# PowerRouting.net
KiCad netlist of a schematic drawn in Altium Designer
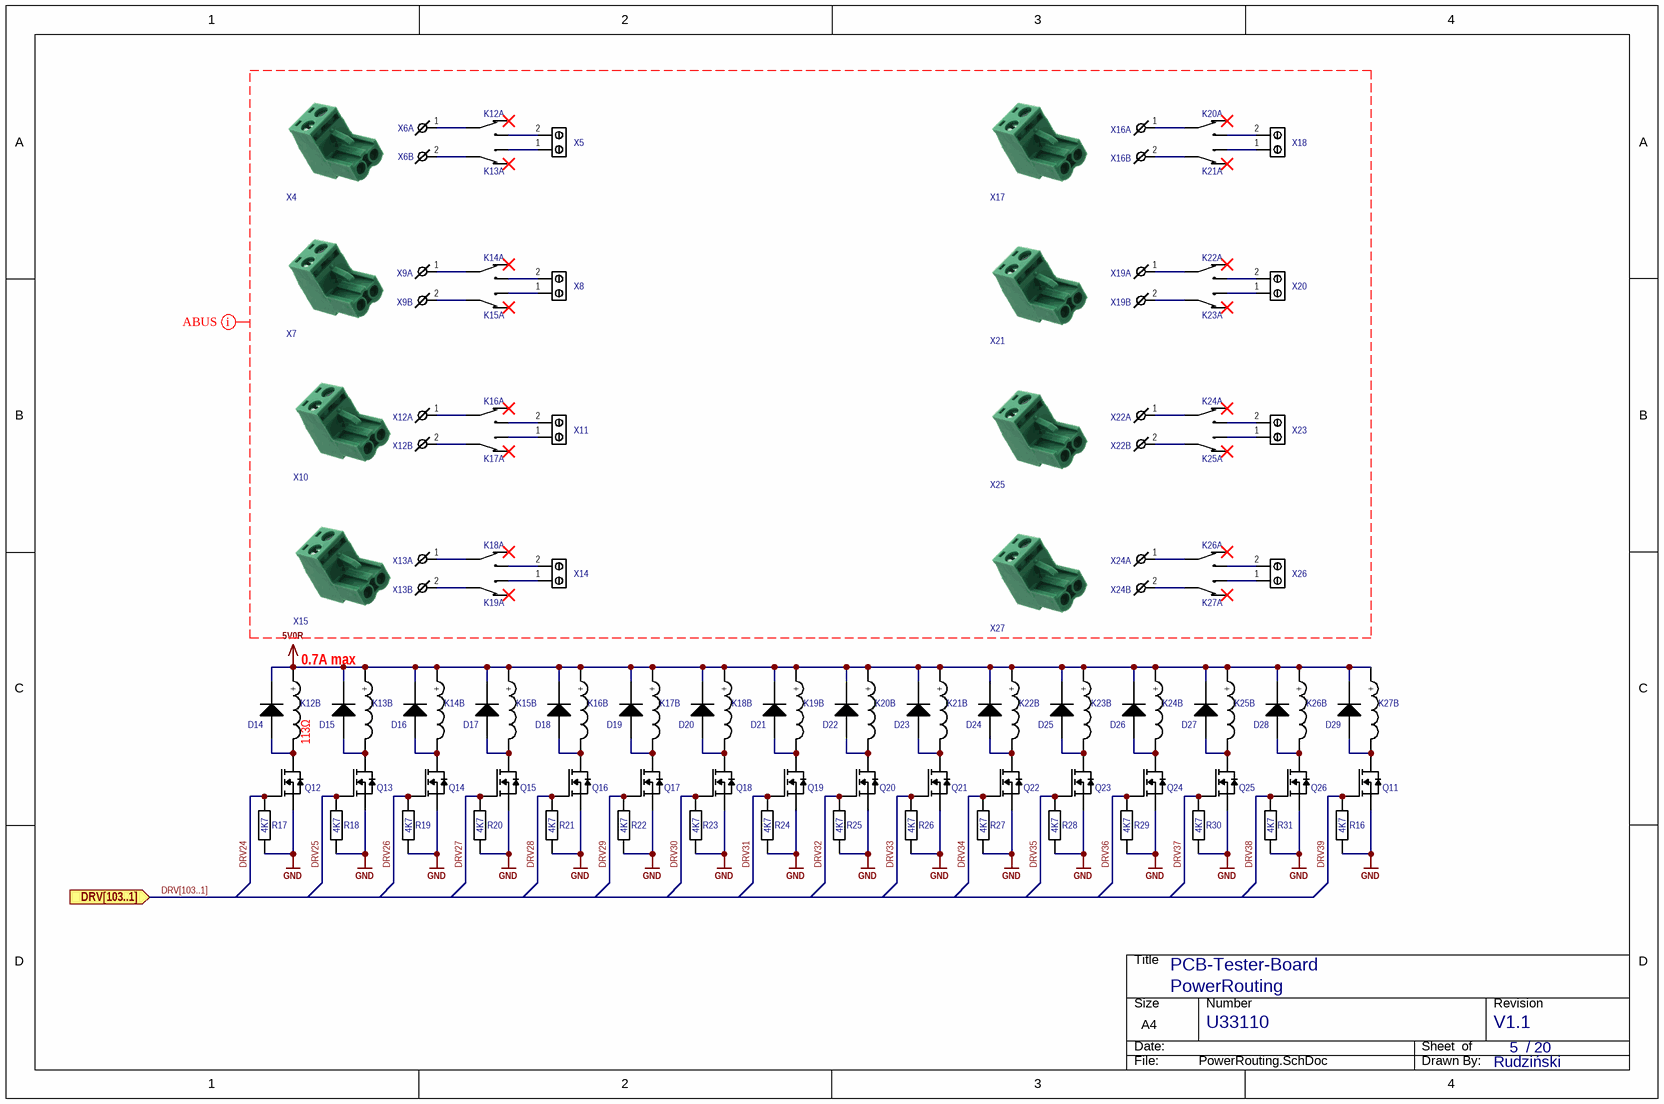
[diagram p0: PowerRouting.SchDoc]

(export (version "E")
  (design (tool "Eeschema 10.0.6"))
  (components
    (comp (ref "D14")
      (value "D")
      (footprint "SOD123")
      (description "DIODE GEN PURP 100V 300MA SOD123")
      (fields
        (field (name "02. DISTRIBUTOR PART NUMBER") "1N4148W-FDICT-ND")
        (field (name "07. MANUFACTURER  PART NUMBER") "1N4148W-7-F")
      )
      (libsource (lib "PCB-Tester-Board-V1") (part "1N4148W"))
    )
    (comp (ref "D15")
      (value "D")
      (footprint "SOD123")
      (description "DIODE GEN PURP 100V 300MA SOD123")
      (fields
        (field (name "02. DISTRIBUTOR PART NUMBER") "1N4148W-FDICT-ND")
        (field (name "07. MANUFACTURER  PART NUMBER") "1N4148W-7-F")
      )
      (libsource (lib "PCB-Tester-Board-V1") (part "1N4148W"))
    )
    (comp (ref "D16")
      (value "D")
      (footprint "SOD123")
      (description "DIODE GEN PURP 100V 300MA SOD123")
      (fields
        (field (name "02. DISTRIBUTOR PART NUMBER") "1N4148W-FDICT-ND")
        (field (name "07. MANUFACTURER  PART NUMBER") "1N4148W-7-F")
      )
      (libsource (lib "PCB-Tester-Board-V1") (part "1N4148W"))
    )
    (comp (ref "D17")
      (value "D")
      (footprint "SOD123")
      (description "DIODE GEN PURP 100V 300MA SOD123")
      (fields
        (field (name "02. DISTRIBUTOR PART NUMBER") "1N4148W-FDICT-ND")
        (field (name "07. MANUFACTURER  PART NUMBER") "1N4148W-7-F")
      )
      (libsource (lib "PCB-Tester-Board-V1") (part "1N4148W"))
    )
    (comp (ref "D18")
      (value "D")
      (footprint "SOD123")
      (description "DIODE GEN PURP 100V 300MA SOD123")
      (fields
        (field (name "02. DISTRIBUTOR PART NUMBER") "1N4148W-FDICT-ND")
        (field (name "07. MANUFACTURER  PART NUMBER") "1N4148W-7-F")
      )
      (libsource (lib "PCB-Tester-Board-V1") (part "1N4148W"))
    )
    (comp (ref "D19")
      (value "D")
      (footprint "SOD123")
      (description "DIODE GEN PURP 100V 300MA SOD123")
      (fields
        (field (name "02. DISTRIBUTOR PART NUMBER") "1N4148W-FDICT-ND")
        (field (name "07. MANUFACTURER  PART NUMBER") "1N4148W-7-F")
      )
      (libsource (lib "PCB-Tester-Board-V1") (part "1N4148W"))
    )
    (comp (ref "D20")
      (value "D")
      (footprint "SOD123")
      (description "DIODE GEN PURP 100V 300MA SOD123")
      (fields
        (field (name "02. DISTRIBUTOR PART NUMBER") "1N4148W-FDICT-ND")
        (field (name "07. MANUFACTURER  PART NUMBER") "1N4148W-7-F")
      )
      (libsource (lib "PCB-Tester-Board-V1") (part "1N4148W"))
    )
    (comp (ref "D21")
      (value "D")
      (footprint "SOD123")
      (description "DIODE GEN PURP 100V 300MA SOD123")
      (fields
        (field (name "02. DISTRIBUTOR PART NUMBER") "1N4148W-FDICT-ND")
        (field (name "07. MANUFACTURER  PART NUMBER") "1N4148W-7-F")
      )
      (libsource (lib "PCB-Tester-Board-V1") (part "1N4148W"))
    )
    (comp (ref "D22")
      (value "D")
      (footprint "SOD123")
      (description "DIODE GEN PURP 100V 300MA SOD123")
      (fields
        (field (name "02. DISTRIBUTOR PART NUMBER") "1N4148W-FDICT-ND")
        (field (name "07. MANUFACTURER  PART NUMBER") "1N4148W-7-F")
      )
      (libsource (lib "PCB-Tester-Board-V1") (part "1N4148W"))
    )
    (comp (ref "D23")
      (value "D")
      (footprint "SOD123")
      (description "DIODE GEN PURP 100V 300MA SOD123")
      (fields
        (field (name "02. DISTRIBUTOR PART NUMBER") "1N4148W-FDICT-ND")
        (field (name "07. MANUFACTURER  PART NUMBER") "1N4148W-7-F")
      )
      (libsource (lib "PCB-Tester-Board-V1") (part "1N4148W"))
    )
    (comp (ref "D24")
      (value "D")
      (footprint "SOD123")
      (description "DIODE GEN PURP 100V 300MA SOD123")
      (fields
        (field (name "02. DISTRIBUTOR PART NUMBER") "1N4148W-FDICT-ND")
        (field (name "07. MANUFACTURER  PART NUMBER") "1N4148W-7-F")
      )
      (libsource (lib "PCB-Tester-Board-V1") (part "1N4148W"))
    )
    (comp (ref "D25")
      (value "D")
      (footprint "SOD123")
      (description "DIODE GEN PURP 100V 300MA SOD123")
      (fields
        (field (name "02. DISTRIBUTOR PART NUMBER") "1N4148W-FDICT-ND")
        (field (name "07. MANUFACTURER  PART NUMBER") "1N4148W-7-F")
      )
      (libsource (lib "PCB-Tester-Board-V1") (part "1N4148W"))
    )
    (comp (ref "D26")
      (value "D")
      (footprint "SOD123")
      (description "DIODE GEN PURP 100V 300MA SOD123")
      (fields
        (field (name "02. DISTRIBUTOR PART NUMBER") "1N4148W-FDICT-ND")
        (field (name "07. MANUFACTURER  PART NUMBER") "1N4148W-7-F")
      )
      (libsource (lib "PCB-Tester-Board-V1") (part "1N4148W"))
    )
    (comp (ref "D27")
      (value "D")
      (footprint "SOD123")
      (description "DIODE GEN PURP 100V 300MA SOD123")
      (fields
        (field (name "02. DISTRIBUTOR PART NUMBER") "1N4148W-FDICT-ND")
        (field (name "07. MANUFACTURER  PART NUMBER") "1N4148W-7-F")
      )
      (libsource (lib "PCB-Tester-Board-V1") (part "1N4148W"))
    )
    (comp (ref "D28")
      (value "D")
      (footprint "SOD123")
      (description "DIODE GEN PURP 100V 300MA SOD123")
      (fields
        (field (name "02. DISTRIBUTOR PART NUMBER") "1N4148W-FDICT-ND")
        (field (name "07. MANUFACTURER  PART NUMBER") "1N4148W-7-F")
      )
      (libsource (lib "PCB-Tester-Board-V1") (part "1N4148W"))
    )
    (comp (ref "D29")
      (value "D")
      (footprint "SOD123")
      (description "DIODE GEN PURP 100V 300MA SOD123")
      (fields
        (field (name "02. DISTRIBUTOR PART NUMBER") "1N4148W-FDICT-ND")
        (field (name "07. MANUFACTURER  PART NUMBER") "1N4148W-7-F")
      )
      (libsource (lib "PCB-Tester-Board-V1") (part "1N4148W"))
    )
    (comp (ref "K12")
      (value "K")
      (footprint "HF118F005-1ZS1")
      (description "5V Power Relay, switch over")
      (fields
        (field (name "02. DISTRIBUTOR PART NUMBER") "176-2821")
        (field (name "07. MANUFACTURER  PART NUMBER") "HF118F/005-1ZS1T(136)")
        (field (name "COIL RESISTANCE") "113Ω")
        (field (name "13. CREATED DATE/NAME") "AUG2018/Hören")
      )
      (libsource (lib "chickenfood") (part "HF118F005-1ZS1"))
    )
    (comp (ref "K13")
      (value "K")
      (footprint "HF118F005-1ZS1")
      (description "5V Power Relay, switch over")
      (fields
        (field (name "02. DISTRIBUTOR PART NUMBER") "176-2821")
        (field (name "07. MANUFACTURER  PART NUMBER") "HF118F/005-1ZS1T(136)")
        (field (name "13. CREATED DATE/NAME") "AUG2018/Hören")
      )
      (libsource (lib "chickenfood") (part "HF118F005-1ZS1"))
    )
    (comp (ref "K14")
      (value "K")
      (footprint "HF118F005-1ZS1")
      (description "5V Power Relay, switch over")
      (fields
        (field (name "02. DISTRIBUTOR PART NUMBER") "176-2821")
        (field (name "07. MANUFACTURER  PART NUMBER") "HF118F/005-1ZS1T(136)")
        (field (name "13. CREATED DATE/NAME") "AUG2018/Hören")
      )
      (libsource (lib "chickenfood") (part "HF118F005-1ZS1"))
    )
    (comp (ref "K15")
      (value "K")
      (footprint "HF118F005-1ZS1")
      (description "5V Power Relay, switch over")
      (fields
        (field (name "02. DISTRIBUTOR PART NUMBER") "176-2821")
        (field (name "07. MANUFACTURER  PART NUMBER") "HF118F/005-1ZS1T(136)")
        (field (name "13. CREATED DATE/NAME") "AUG2018/Hören")
      )
      (libsource (lib "chickenfood") (part "HF118F005-1ZS1"))
    )
    (comp (ref "K16")
      (value "K")
      (footprint "HF118F005-1ZS1")
      (description "5V Power Relay, switch over")
      (fields
        (field (name "02. DISTRIBUTOR PART NUMBER") "176-2821")
        (field (name "07. MANUFACTURER  PART NUMBER") "HF118F/005-1ZS1T(136)")
        (field (name "13. CREATED DATE/NAME") "AUG2018/Hören")
      )
      (libsource (lib "chickenfood") (part "HF118F005-1ZS1"))
    )
    (comp (ref "K17")
      (value "K")
      (footprint "HF118F005-1ZS1")
      (description "5V Power Relay, switch over")
      (fields
        (field (name "02. DISTRIBUTOR PART NUMBER") "176-2821")
        (field (name "07. MANUFACTURER  PART NUMBER") "HF118F/005-1ZS1T(136)")
        (field (name "13. CREATED DATE/NAME") "AUG2018/Hören")
      )
      (libsource (lib "chickenfood") (part "HF118F005-1ZS1"))
    )
    (comp (ref "K18")
      (value "K")
      (footprint "HF118F005-1ZS1")
      (description "5V Power Relay, switch over")
      (fields
        (field (name "02. DISTRIBUTOR PART NUMBER") "176-2821")
        (field (name "07. MANUFACTURER  PART NUMBER") "HF118F/005-1ZS1T(136)")
        (field (name "13. CREATED DATE/NAME") "AUG2018/Hören")
      )
      (libsource (lib "chickenfood") (part "HF118F005-1ZS1"))
    )
    (comp (ref "K19")
      (value "K")
      (footprint "HF118F005-1ZS1")
      (description "5V Power Relay, switch over")
      (fields
        (field (name "02. DISTRIBUTOR PART NUMBER") "176-2821")
        (field (name "07. MANUFACTURER  PART NUMBER") "HF118F/005-1ZS1T(136)")
        (field (name "13. CREATED DATE/NAME") "AUG2018/Hören")
      )
      (libsource (lib "chickenfood") (part "HF118F005-1ZS1"))
    )
    (comp (ref "K20")
      (value "K")
      (footprint "HF118F005-1ZS1")
      (description "5V Power Relay, switch over")
      (fields
        (field (name "02. DISTRIBUTOR PART NUMBER") "176-2821")
        (field (name "07. MANUFACTURER  PART NUMBER") "HF118F/005-1ZS1T(136)")
        (field (name "13. CREATED DATE/NAME") "AUG2018/Hören")
      )
      (libsource (lib "chickenfood") (part "HF118F005-1ZS1"))
    )
    (comp (ref "K21")
      (value "K")
      (footprint "HF118F005-1ZS1")
      (description "5V Power Relay, switch over")
      (fields
        (field (name "02. DISTRIBUTOR PART NUMBER") "176-2821")
        (field (name "07. MANUFACTURER  PART NUMBER") "HF118F/005-1ZS1T(136)")
        (field (name "13. CREATED DATE/NAME") "AUG2018/Hören")
      )
      (libsource (lib "chickenfood") (part "HF118F005-1ZS1"))
    )
    (comp (ref "K22")
      (value "K")
      (footprint "HF118F005-1ZS1")
      (description "5V Power Relay, switch over")
      (fields
        (field (name "02. DISTRIBUTOR PART NUMBER") "176-2821")
        (field (name "07. MANUFACTURER  PART NUMBER") "HF118F/005-1ZS1T(136)")
        (field (name "13. CREATED DATE/NAME") "AUG2018/Hören")
      )
      (libsource (lib "chickenfood") (part "HF118F005-1ZS1"))
    )
    (comp (ref "K23")
      (value "K")
      (footprint "HF118F005-1ZS1")
      (description "5V Power Relay, switch over")
      (fields
        (field (name "02. DISTRIBUTOR PART NUMBER") "176-2821")
        (field (name "07. MANUFACTURER  PART NUMBER") "HF118F/005-1ZS1T(136)")
        (field (name "13. CREATED DATE/NAME") "AUG2018/Hören")
      )
      (libsource (lib "") (part "HF118F005-1ZS1_1"))
    )
    (comp (ref "K24")
      (value "K")
      (footprint "HF118F005-1ZS1")
      (description "5V Power Relay, switch over")
      (fields
        (field (name "02. DISTRIBUTOR PART NUMBER") "176-2821")
        (field (name "07. MANUFACTURER  PART NUMBER") "HF118F/005-1ZS1T(136)")
        (field (name "13. CREATED DATE/NAME") "AUG2018/Hören")
      )
      (libsource (lib "chickenfood") (part "HF118F005-1ZS1"))
    )
    (comp (ref "K25")
      (value "K")
      (footprint "HF118F005-1ZS1")
      (description "5V Power Relay, switch over")
      (fields
        (field (name "02. DISTRIBUTOR PART NUMBER") "176-2821")
        (field (name "07. MANUFACTURER  PART NUMBER") "HF118F/005-1ZS1T(136)")
        (field (name "13. CREATED DATE/NAME") "AUG2018/Hören")
      )
      (libsource (lib "") (part "HF118F005-1ZS1_1"))
    )
    (comp (ref "K26")
      (value "K")
      (footprint "HF118F005-1ZS1")
      (description "5V Power Relay, switch over")
      (fields
        (field (name "02. DISTRIBUTOR PART NUMBER") "176-2821")
        (field (name "07. MANUFACTURER  PART NUMBER") "HF118F/005-1ZS1T(136)")
        (field (name "13. CREATED DATE/NAME") "AUG2018/Hören")
      )
      (libsource (lib "chickenfood") (part "HF118F005-1ZS1"))
    )
    (comp (ref "K27")
      (value "K")
      (footprint "HF118F005-1ZS1")
      (description "5V Power Relay, switch over")
      (fields
        (field (name "02. DISTRIBUTOR PART NUMBER") "176-2821")
        (field (name "07. MANUFACTURER  PART NUMBER") "HF118F/005-1ZS1T(136)")
        (field (name "13. CREATED DATE/NAME") "AUG2018/Hören")
      )
      (libsource (lib "") (part "HF118F005-1ZS1_1"))
    )
    (comp (ref "Q11")
      (value "Q")
      (footprint "SOT23-3")
      (description "MOSFET N-CH 25V 680MA SOT-23")
      (fields
        (field (name "02. DISTRIBUTOR PART NUMBER") "FDV303NDKR-ND")
        (field (name "07. MANUFACTURER  PART NUMBER") "FDV303N")
        (field (name "13. CREATED DATE/NAME") "AUG 2018 / Hören")
      )
      (libsource (lib "SCT8-Board1") (part "FDV303N"))
    )
    (comp (ref "Q12")
      (value "Q")
      (footprint "SOT23-3")
      (description "MOSFET N-CH 25V 680MA SOT-23")
      (fields
        (field (name "02. DISTRIBUTOR PART NUMBER") "FDV303NDKR-ND")
        (field (name "07. MANUFACTURER  PART NUMBER") "FDV303N")
        (field (name "13. CREATED DATE/NAME") "AUG 2018 / Hören")
      )
      (libsource (lib "SCT8-Board1") (part "FDV303N"))
    )
    (comp (ref "Q13")
      (value "Q")
      (footprint "SOT23-3")
      (description "MOSFET N-CH 25V 680MA SOT-23")
      (fields
        (field (name "02. DISTRIBUTOR PART NUMBER") "FDV303NDKR-ND")
        (field (name "07. MANUFACTURER  PART NUMBER") "FDV303N")
        (field (name "13. CREATED DATE/NAME") "AUG 2018 / Hören")
      )
      (libsource (lib "SCT8-Board1") (part "FDV303N"))
    )
    (comp (ref "Q14")
      (value "Q")
      (footprint "SOT23-3")
      (description "MOSFET N-CH 25V 680MA SOT-23")
      (fields
        (field (name "02. DISTRIBUTOR PART NUMBER") "FDV303NDKR-ND")
        (field (name "07. MANUFACTURER  PART NUMBER") "FDV303N")
        (field (name "13. CREATED DATE/NAME") "AUG 2018 / Hören")
      )
      (libsource (lib "SCT8-Board1") (part "FDV303N"))
    )
    (comp (ref "Q15")
      (value "Q")
      (footprint "SOT23-3")
      (description "MOSFET N-CH 25V 680MA SOT-23")
      (fields
        (field (name "02. DISTRIBUTOR PART NUMBER") "FDV303NDKR-ND")
        (field (name "07. MANUFACTURER  PART NUMBER") "FDV303N")
        (field (name "13. CREATED DATE/NAME") "AUG 2018 / Hören")
      )
      (libsource (lib "SCT8-Board1") (part "FDV303N"))
    )
    (comp (ref "Q16")
      (value "Q")
      (footprint "SOT23-3")
      (description "MOSFET N-CH 25V 680MA SOT-23")
      (fields
        (field (name "02. DISTRIBUTOR PART NUMBER") "FDV303NDKR-ND")
        (field (name "07. MANUFACTURER  PART NUMBER") "FDV303N")
        (field (name "13. CREATED DATE/NAME") "AUG 2018 / Hören")
      )
      (libsource (lib "SCT8-Board1") (part "FDV303N"))
    )
    (comp (ref "Q17")
      (value "Q")
      (footprint "SOT23-3")
      (description "MOSFET N-CH 25V 680MA SOT-23")
      (fields
        (field (name "02. DISTRIBUTOR PART NUMBER") "FDV303NDKR-ND")
        (field (name "07. MANUFACTURER  PART NUMBER") "FDV303N")
        (field (name "13. CREATED DATE/NAME") "AUG 2018 / Hören")
      )
      (libsource (lib "SCT8-Board1") (part "FDV303N"))
    )
    (comp (ref "Q18")
      (value "Q")
      (footprint "SOT23-3")
      (description "MOSFET N-CH 25V 680MA SOT-23")
      (fields
        (field (name "02. DISTRIBUTOR PART NUMBER") "FDV303NDKR-ND")
        (field (name "07. MANUFACTURER  PART NUMBER") "FDV303N")
        (field (name "13. CREATED DATE/NAME") "AUG 2018 / Hören")
      )
      (libsource (lib "SCT8-Board1") (part "FDV303N"))
    )
    (comp (ref "Q19")
      (value "Q")
      (footprint "SOT23-3")
      (description "MOSFET N-CH 25V 680MA SOT-23")
      (fields
        (field (name "02. DISTRIBUTOR PART NUMBER") "FDV303NDKR-ND")
        (field (name "07. MANUFACTURER  PART NUMBER") "FDV303N")
        (field (name "13. CREATED DATE/NAME") "AUG 2018 / Hören")
      )
      (libsource (lib "SCT8-Board1") (part "FDV303N"))
    )
    (comp (ref "Q20")
      (value "Q")
      (footprint "SOT23-3")
      (description "MOSFET N-CH 25V 680MA SOT-23")
      (fields
        (field (name "02. DISTRIBUTOR PART NUMBER") "FDV303NDKR-ND")
        (field (name "07. MANUFACTURER  PART NUMBER") "FDV303N")
        (field (name "13. CREATED DATE/NAME") "AUG 2018 / Hören")
      )
      (libsource (lib "SCT8-Board1") (part "FDV303N"))
    )
    (comp (ref "Q21")
      (value "Q")
      (footprint "SOT23-3")
      (description "MOSFET N-CH 25V 680MA SOT-23")
      (fields
        (field (name "02. DISTRIBUTOR PART NUMBER") "FDV303NDKR-ND")
        (field (name "07. MANUFACTURER  PART NUMBER") "FDV303N")
        (field (name "13. CREATED DATE/NAME") "AUG 2018 / Hören")
      )
      (libsource (lib "SCT8-Board1") (part "FDV303N"))
    )
    (comp (ref "Q22")
      (value "Q")
      (footprint "SOT23-3")
      (description "MOSFET N-CH 25V 680MA SOT-23")
      (fields
        (field (name "02. DISTRIBUTOR PART NUMBER") "FDV303NDKR-ND")
        (field (name "07. MANUFACTURER  PART NUMBER") "FDV303N")
        (field (name "13. CREATED DATE/NAME") "AUG 2018 / Hören")
      )
      (libsource (lib "SCT8-Board1") (part "FDV303N"))
    )
    (comp (ref "Q23")
      (value "Q")
      (footprint "SOT23-3")
      (description "MOSFET N-CH 25V 680MA SOT-23")
      (fields
        (field (name "02. DISTRIBUTOR PART NUMBER") "FDV303NDKR-ND")
        (field (name "07. MANUFACTURER  PART NUMBER") "FDV303N")
        (field (name "13. CREATED DATE/NAME") "AUG 2018 / Hören")
      )
      (libsource (lib "SCT8-Board1") (part "FDV303N"))
    )
    (comp (ref "Q24")
      (value "Q")
      (footprint "SOT23-3")
      (description "MOSFET N-CH 25V 680MA SOT-23")
      (fields
        (field (name "02. DISTRIBUTOR PART NUMBER") "FDV303NDKR-ND")
        (field (name "07. MANUFACTURER  PART NUMBER") "FDV303N")
        (field (name "13. CREATED DATE/NAME") "AUG 2018 / Hören")
      )
      (libsource (lib "SCT8-Board1") (part "FDV303N"))
    )
    (comp (ref "Q25")
      (value "Q")
      (footprint "SOT23-3")
      (description "MOSFET N-CH 25V 680MA SOT-23")
      (fields
        (field (name "02. DISTRIBUTOR PART NUMBER") "FDV303NDKR-ND")
        (field (name "07. MANUFACTURER  PART NUMBER") "FDV303N")
        (field (name "13. CREATED DATE/NAME") "AUG 2018 / Hören")
      )
      (libsource (lib "SCT8-Board1") (part "FDV303N"))
    )
    (comp (ref "Q26")
      (value "Q")
      (footprint "SOT23-3")
      (description "MOSFET N-CH 25V 680MA SOT-23")
      (fields
        (field (name "02. DISTRIBUTOR PART NUMBER") "FDV303NDKR-ND")
        (field (name "07. MANUFACTURER  PART NUMBER") "FDV303N")
        (field (name "13. CREATED DATE/NAME") "AUG 2018 / Hören")
      )
      (libsource (lib "SCT8-Board1") (part "FDV303N"))
    )
    (comp (ref "R16")
      (value "4K7")
      (footprint "R0603 Reflow")
      (description "RES SMD 4.7K OHM 1% 1/10W 0603")
      (fields
        (field (name "TOLERANCE") "±1%")
        (field (name "02. DISTRIBUTOR PART NUMBER") "311-4.70KHRCT-ND")
        (field (name "13. CREATED DATE/NAME") "AUG2018/Hören")
      )
      (libsource (lib "chickenfood") (part "R"))
    )
    (comp (ref "R17")
      (value "4K7")
      (footprint "R0603 Reflow")
      (description "RES SMD 4.7K OHM 1% 1/10W 0603")
      (fields
        (field (name "TOLERANCE") "±1%")
        (field (name "02. DISTRIBUTOR PART NUMBER") "311-4.70KHRCT-ND")
        (field (name "13. CREATED DATE/NAME") "AUG2018/Hören")
      )
      (libsource (lib "chickenfood") (part "R"))
    )
    (comp (ref "R18")
      (value "4K7")
      (footprint "R0603 Reflow")
      (description "RES SMD 4.7K OHM 1% 1/10W 0603")
      (fields
        (field (name "TOLERANCE") "±1%")
        (field (name "02. DISTRIBUTOR PART NUMBER") "311-4.70KHRCT-ND")
        (field (name "13. CREATED DATE/NAME") "AUG2018/Hören")
      )
      (libsource (lib "chickenfood") (part "R"))
    )
    (comp (ref "R19")
      (value "4K7")
      (footprint "R0603 Reflow")
      (description "RES SMD 4.7K OHM 1% 1/10W 0603")
      (fields
        (field (name "TOLERANCE") "±1%")
        (field (name "02. DISTRIBUTOR PART NUMBER") "311-4.70KHRCT-ND")
        (field (name "13. CREATED DATE/NAME") "AUG2018/Hören")
      )
      (libsource (lib "chickenfood") (part "R"))
    )
    (comp (ref "R20")
      (value "4K7")
      (footprint "R0603 Reflow")
      (description "RES SMD 4.7K OHM 1% 1/10W 0603")
      (fields
        (field (name "TOLERANCE") "±1%")
        (field (name "02. DISTRIBUTOR PART NUMBER") "311-4.70KHRCT-ND")
        (field (name "13. CREATED DATE/NAME") "AUG2018/Hören")
      )
      (libsource (lib "chickenfood") (part "R"))
    )
    (comp (ref "R21")
      (value "4K7")
      (footprint "R0603 Reflow")
      (description "RES SMD 4.7K OHM 1% 1/10W 0603")
      (fields
        (field (name "TOLERANCE") "±1%")
        (field (name "02. DISTRIBUTOR PART NUMBER") "311-4.70KHRCT-ND")
        (field (name "13. CREATED DATE/NAME") "AUG2018/Hören")
      )
      (libsource (lib "chickenfood") (part "R"))
    )
    (comp (ref "R22")
      (value "4K7")
      (footprint "R0603 Reflow")
      (description "RES SMD 4.7K OHM 1% 1/10W 0603")
      (fields
        (field (name "TOLERANCE") "±1%")
        (field (name "02. DISTRIBUTOR PART NUMBER") "311-4.70KHRCT-ND")
        (field (name "13. CREATED DATE/NAME") "AUG2018/Hören")
      )
      (libsource (lib "chickenfood") (part "R"))
    )
    (comp (ref "R23")
      (value "4K7")
      (footprint "R0603 Reflow")
      (description "RES SMD 4.7K OHM 1% 1/10W 0603")
      (fields
        (field (name "TOLERANCE") "±1%")
        (field (name "02. DISTRIBUTOR PART NUMBER") "311-4.70KHRCT-ND")
        (field (name "13. CREATED DATE/NAME") "AUG2018/Hören")
      )
      (libsource (lib "chickenfood") (part "R"))
    )
    (comp (ref "R24")
      (value "4K7")
      (footprint "R0603 Reflow")
      (description "RES SMD 4.7K OHM 1% 1/10W 0603")
      (fields
        (field (name "TOLERANCE") "±1%")
        (field (name "02. DISTRIBUTOR PART NUMBER") "311-4.70KHRCT-ND")
        (field (name "13. CREATED DATE/NAME") "AUG2018/Hören")
      )
      (libsource (lib "chickenfood") (part "R"))
    )
    (comp (ref "R25")
      (value "4K7")
      (footprint "R0603 Reflow")
      (description "RES SMD 4.7K OHM 1% 1/10W 0603")
      (fields
        (field (name "TOLERANCE") "±1%")
        (field (name "02. DISTRIBUTOR PART NUMBER") "311-4.70KHRCT-ND")
        (field (name "13. CREATED DATE/NAME") "AUG2018/Hören")
      )
      (libsource (lib "chickenfood") (part "R"))
    )
    (comp (ref "R26")
      (value "4K7")
      (footprint "R0603 Reflow")
      (description "RES SMD 4.7K OHM 1% 1/10W 0603")
      (fields
        (field (name "TOLERANCE") "±1%")
        (field (name "02. DISTRIBUTOR PART NUMBER") "311-4.70KHRCT-ND")
        (field (name "13. CREATED DATE/NAME") "AUG2018/Hören")
      )
      (libsource (lib "chickenfood") (part "R"))
    )
    (comp (ref "R27")
      (value "4K7")
      (footprint "R0603 Reflow")
      (description "RES SMD 4.7K OHM 1% 1/10W 0603")
      (fields
        (field (name "TOLERANCE") "±1%")
        (field (name "02. DISTRIBUTOR PART NUMBER") "311-4.70KHRCT-ND")
        (field (name "13. CREATED DATE/NAME") "AUG2018/Hören")
      )
      (libsource (lib "chickenfood") (part "R"))
    )
    (comp (ref "R28")
      (value "4K7")
      (footprint "R0603 Reflow")
      (description "RES SMD 4.7K OHM 1% 1/10W 0603")
      (fields
        (field (name "TOLERANCE") "±1%")
        (field (name "02. DISTRIBUTOR PART NUMBER") "311-4.70KHRCT-ND")
        (field (name "13. CREATED DATE/NAME") "AUG2018/Hören")
      )
      (libsource (lib "chickenfood") (part "R"))
    )
    (comp (ref "R29")
      (value "4K7")
      (footprint "R0603 Reflow")
      (description "RES SMD 4.7K OHM 1% 1/10W 0603")
      (fields
        (field (name "TOLERANCE") "±1%")
        (field (name "02. DISTRIBUTOR PART NUMBER") "311-4.70KHRCT-ND")
        (field (name "13. CREATED DATE/NAME") "AUG2018/Hören")
      )
      (libsource (lib "chickenfood") (part "R"))
    )
    (comp (ref "R30")
      (value "4K7")
      (footprint "R0603 Reflow")
      (description "RES SMD 4.7K OHM 1% 1/10W 0603")
      (fields
        (field (name "TOLERANCE") "±1%")
        (field (name "02. DISTRIBUTOR PART NUMBER") "311-4.70KHRCT-ND")
        (field (name "13. CREATED DATE/NAME") "AUG2018/Hören")
      )
      (libsource (lib "chickenfood") (part "R"))
    )
    (comp (ref "R31")
      (value "4K7")
      (footprint "R0603 Reflow")
      (description "RES SMD 4.7K OHM 1% 1/10W 0603")
      (fields
        (field (name "TOLERANCE") "±1%")
        (field (name "02. DISTRIBUTOR PART NUMBER") "311-4.70KHRCT-ND")
        (field (name "13. CREATED DATE/NAME") "AUG2018/Hören")
      )
      (libsource (lib "chickenfood") (part "R"))
    )
    (comp (ref "X4")
      (value "X")
      (footprint "691352710002")
      (description "TERM BLOCK PLUG 2POS STR 5MM")
      (fields
        (field (name "02. DISTRIBUTOR PART NUMBER") "732-2775-ND")
        (field (name "07. MANUFACTURER  PART NUMBER") "691352710002")
        (field (name "13. CREATED DATE/NAME") "??? / Hören")
      )
      (libsource (lib "PCB-Tester-Board-V1") (part "691352710002"))
    )
    (comp (ref "X5")
      (value "X")
      (footprint "1731721")
      (description "TERM BLK 2P SIDE ENT 7.62MM PCB")
      (fields
        (field (name "02. DISTRIBUTOR PART NUMBER") "277-5849-ND")
        (field (name "07. MANUFACTURER  PART NUMBER") "1731721")
        (field (name "13. CREATED DATE/NAME") "JAN 2019 / Hören")
      )
      (libsource (lib "Connectors") (part "1731721"))
    )
    (comp (ref "X6")
      (value "X")
      (footprint "691312710002")
      (description "TERM BLOCK HDR 2POS 90DEG 5MM")
      (fields
        (field (name "02. DISTRIBUTOR PART NUMBER") "732-2805-ND")
        (field (name "07. MANUFACTURER  PART NUMBER") "691312710002")
        (field (name "13. CREATED DATE/NAME") "??? / Hören")
      )
      (libsource (lib "Connectors") (part "691312710002"))
    )
    (comp (ref "X7")
      (value "X")
      (footprint "691352710002")
      (description "TERM BLOCK PLUG 2POS STR 5MM")
      (fields
        (field (name "02. DISTRIBUTOR PART NUMBER") "732-2775-ND")
        (field (name "07. MANUFACTURER  PART NUMBER") "691352710002")
        (field (name "13. CREATED DATE/NAME") "??? / Hören")
      )
      (libsource (lib "PCB-Tester-Board-V1") (part "691352710002"))
    )
    (comp (ref "X8")
      (value "X")
      (footprint "1731721")
      (description "TERM BLK 2P SIDE ENT 7.62MM PCB")
      (fields
        (field (name "02. DISTRIBUTOR PART NUMBER") "277-5849-ND")
        (field (name "07. MANUFACTURER  PART NUMBER") "1731721")
        (field (name "13. CREATED DATE/NAME") "JAN 2019 / Hören")
      )
      (libsource (lib "Connectors") (part "1731721"))
    )
    (comp (ref "X9")
      (value "X")
      (footprint "691312710002")
      (description "TERM BLOCK HDR 2POS 90DEG 5MM")
      (fields
        (field (name "02. DISTRIBUTOR PART NUMBER") "732-2805-ND")
        (field (name "07. MANUFACTURER  PART NUMBER") "691312710002")
        (field (name "13. CREATED DATE/NAME") "??? / Hören")
      )
      (libsource (lib "Connectors") (part "691312710002"))
    )
    (comp (ref "X10")
      (value "X")
      (footprint "691352710002")
      (description "TERM BLOCK PLUG 2POS STR 5MM")
      (fields
        (field (name "02. DISTRIBUTOR PART NUMBER") "732-2775-ND")
        (field (name "07. MANUFACTURER  PART NUMBER") "691352710002")
        (field (name "13. CREATED DATE/NAME") "??? / Hören")
      )
      (libsource (lib "PCB-Tester-Board-V1") (part "691352710002"))
    )
    (comp (ref "X11")
      (value "X")
      (footprint "1731721")
      (description "TERM BLK 2P SIDE ENT 7.62MM PCB")
      (fields
        (field (name "02. DISTRIBUTOR PART NUMBER") "277-5849-ND")
        (field (name "07. MANUFACTURER  PART NUMBER") "1731721")
        (field (name "13. CREATED DATE/NAME") "JAN 2019 / Hören")
      )
      (libsource (lib "Connectors") (part "1731721"))
    )
    (comp (ref "X12")
      (value "X")
      (footprint "691312710002")
      (description "TERM BLOCK HDR 2POS 90DEG 5MM")
      (fields
        (field (name "02. DISTRIBUTOR PART NUMBER") "732-2805-ND")
        (field (name "07. MANUFACTURER  PART NUMBER") "691312710002")
        (field (name "13. CREATED DATE/NAME") "??? / Hören")
      )
      (libsource (lib "Connectors") (part "691312710002"))
    )
    (comp (ref "X13")
      (value "X")
      (footprint "691312710002")
      (description "TERM BLOCK HDR 2POS 90DEG 5MM")
      (fields
        (field (name "02. DISTRIBUTOR PART NUMBER") "732-2805-ND")
        (field (name "07. MANUFACTURER  PART NUMBER") "691312710002")
        (field (name "13. CREATED DATE/NAME") "??? / Hören")
      )
      (libsource (lib "Connectors") (part "691312710002"))
    )
    (comp (ref "X14")
      (value "X")
      (footprint "1731721")
      (description "TERM BLK 2P SIDE ENT 7.62MM PCB")
      (fields
        (field (name "02. DISTRIBUTOR PART NUMBER") "277-5849-ND")
        (field (name "07. MANUFACTURER  PART NUMBER") "1731721")
        (field (name "13. CREATED DATE/NAME") "JAN 2019 / Hören")
      )
      (libsource (lib "Connectors") (part "1731721"))
    )
    (comp (ref "X15")
      (value "X")
      (footprint "691352710002")
      (description "TERM BLOCK PLUG 2POS STR 5MM")
      (fields
        (field (name "02. DISTRIBUTOR PART NUMBER") "732-2775-ND")
        (field (name "07. MANUFACTURER  PART NUMBER") "691352710002")
        (field (name "13. CREATED DATE/NAME") "??? / Hören")
      )
      (libsource (lib "PCB-Tester-Board-V1") (part "691352710002"))
    )
    (comp (ref "X16")
      (value "X")
      (footprint "691312710002")
      (description "TERM BLOCK HDR 2POS 90DEG 5MM")
      (fields
        (field (name "02. DISTRIBUTOR PART NUMBER") "732-2805-ND")
        (field (name "07. MANUFACTURER  PART NUMBER") "691312710002")
        (field (name "13. CREATED DATE/NAME") "??? / Hören")
      )
      (libsource (lib "Connectors") (part "691312710002"))
    )
    (comp (ref "X17")
      (value "X")
      (footprint "691352710002")
      (description "TERM BLOCK PLUG 2POS STR 5MM")
      (fields
        (field (name "02. DISTRIBUTOR PART NUMBER") "732-2775-ND")
        (field (name "07. MANUFACTURER  PART NUMBER") "691352710002")
        (field (name "13. CREATED DATE/NAME") "??? / Hören")
      )
      (libsource (lib "PCB-Tester-Board-V1") (part "691352710002"))
    )
    (comp (ref "X18")
      (value "X")
      (footprint "1731721")
      (description "TERM BLK 2P SIDE ENT 7.62MM PCB")
      (fields
        (field (name "02. DISTRIBUTOR PART NUMBER") "277-5849-ND")
        (field (name "07. MANUFACTURER  PART NUMBER") "1731721")
        (field (name "13. CREATED DATE/NAME") "JAN 2019 / Hören")
      )
      (libsource (lib "Connectors") (part "1731721"))
    )
    (comp (ref "X19")
      (value "X")
      (footprint "691312710002")
      (description "TERM BLOCK HDR 2POS 90DEG 5MM")
      (fields
        (field (name "02. DISTRIBUTOR PART NUMBER") "732-2805-ND")
        (field (name "07. MANUFACTURER  PART NUMBER") "691312710002")
        (field (name "13. CREATED DATE/NAME") "??? / Hören")
      )
      (libsource (lib "Connectors") (part "691312710002"))
    )
    (comp (ref "X20")
      (value "X")
      (footprint "1731721")
      (description "TERM BLK 2P SIDE ENT 7.62MM PCB")
      (fields
        (field (name "02. DISTRIBUTOR PART NUMBER") "277-5849-ND")
        (field (name "07. MANUFACTURER  PART NUMBER") "1731721")
        (field (name "13. CREATED DATE/NAME") "JAN 2019 / Hören")
      )
      (libsource (lib "Connectors") (part "1731721"))
    )
    (comp (ref "X21")
      (value "X")
      (footprint "691352710002")
      (description "TERM BLOCK PLUG 2POS STR 5MM")
      (fields
        (field (name "02. DISTRIBUTOR PART NUMBER") "732-2775-ND")
        (field (name "07. MANUFACTURER  PART NUMBER") "691352710002")
        (field (name "13. CREATED DATE/NAME") "??? / Hören")
      )
      (libsource (lib "PCB-Tester-Board-V1") (part "691352710002"))
    )
    (comp (ref "X22")
      (value "X")
      (footprint "691312710002")
      (description "TERM BLOCK HDR 2POS 90DEG 5MM")
      (fields
        (field (name "02. DISTRIBUTOR PART NUMBER") "732-2805-ND")
        (field (name "07. MANUFACTURER  PART NUMBER") "691312710002")
        (field (name "13. CREATED DATE/NAME") "??? / Hören")
      )
      (libsource (lib "Connectors") (part "691312710002"))
    )
    (comp (ref "X23")
      (value "X")
      (footprint "1731721")
      (description "TERM BLK 2P SIDE ENT 7.62MM PCB")
      (fields
        (field (name "02. DISTRIBUTOR PART NUMBER") "277-5849-ND")
        (field (name "07. MANUFACTURER  PART NUMBER") "1731721")
        (field (name "13. CREATED DATE/NAME") "JAN 2019 / Hören")
      )
      (libsource (lib "Connectors") (part "1731721"))
    )
    (comp (ref "X24")
      (value "X")
      (footprint "691312710002")
      (description "TERM BLOCK HDR 2POS 90DEG 5MM")
      (fields
        (field (name "02. DISTRIBUTOR PART NUMBER") "732-2805-ND")
        (field (name "07. MANUFACTURER  PART NUMBER") "691312710002")
        (field (name "13. CREATED DATE/NAME") "??? / Hören")
      )
      (libsource (lib "Connectors") (part "691312710002"))
    )
    (comp (ref "X25")
      (value "X")
      (footprint "691352710002")
      (description "TERM BLOCK PLUG 2POS STR 5MM")
      (fields
        (field (name "02. DISTRIBUTOR PART NUMBER") "732-2775-ND")
        (field (name "07. MANUFACTURER  PART NUMBER") "691352710002")
        (field (name "13. CREATED DATE/NAME") "??? / Hören")
      )
      (libsource (lib "PCB-Tester-Board-V1") (part "691352710002"))
    )
    (comp (ref "X26")
      (value "X")
      (footprint "1731721")
      (description "TERM BLK 2P SIDE ENT 7.62MM PCB")
      (fields
        (field (name "02. DISTRIBUTOR PART NUMBER") "277-5849-ND")
        (field (name "07. MANUFACTURER  PART NUMBER") "1731721")
        (field (name "13. CREATED DATE/NAME") "JAN 2019 / Hören")
      )
      (libsource (lib "Connectors") (part "1731721"))
    )
    (comp (ref "X27")
      (value "X")
      (footprint "691352710002")
      (description "TERM BLOCK PLUG 2POS STR 5MM")
      (fields
        (field (name "02. DISTRIBUTOR PART NUMBER") "732-2775-ND")
        (field (name "07. MANUFACTURER  PART NUMBER") "691352710002")
        (field (name "13. CREATED DATE/NAME") "??? / Hören")
      )
      (libsource (lib "PCB-Tester-Board-V1") (part "691352710002"))
    )
  )
  (nets
    (net (code "88") (name "/DRV24") (class "Default")
      (node (ref "Q12") (pin "1") (pinfunction "G_1") (pintype "passive"))
      (node (ref "R17") (pin "2") (pinfunction "2_2") (pintype "passive"))
    )
    (net (code "89") (name "/DRV25") (class "Default")
      (node (ref "Q13") (pin "1") (pinfunction "G_1") (pintype "passive"))
      (node (ref "R18") (pin "2") (pinfunction "2_2") (pintype "passive"))
    )
    (net (code "90") (name "/DRV26") (class "Default")
      (node (ref "Q14") (pin "1") (pinfunction "G_1") (pintype "passive"))
      (node (ref "R19") (pin "2") (pinfunction "2_2") (pintype "passive"))
    )
    (net (code "91") (name "/DRV27") (class "Default")
      (node (ref "Q15") (pin "1") (pinfunction "G_1") (pintype "passive"))
      (node (ref "R20") (pin "2") (pinfunction "2_2") (pintype "passive"))
    )
    (net (code "92") (name "/DRV28") (class "Default")
      (node (ref "Q16") (pin "1") (pinfunction "G_1") (pintype "passive"))
      (node (ref "R21") (pin "2") (pinfunction "2_2") (pintype "passive"))
    )
    (net (code "93") (name "/DRV29") (class "Default")
      (node (ref "Q17") (pin "1") (pinfunction "G_1") (pintype "passive"))
      (node (ref "R22") (pin "2") (pinfunction "2_2") (pintype "passive"))
    )
    (net (code "94") (name "/DRV30") (class "Default")
      (node (ref "Q18") (pin "1") (pinfunction "G_1") (pintype "passive"))
      (node (ref "R23") (pin "2") (pinfunction "2_2") (pintype "passive"))
    )
    (net (code "95") (name "/DRV31") (class "Default")
      (node (ref "Q19") (pin "1") (pinfunction "G_1") (pintype "passive"))
      (node (ref "R24") (pin "2") (pinfunction "2_2") (pintype "passive"))
    )
    (net (code "96") (name "/DRV32") (class "Default")
      (node (ref "Q20") (pin "1") (pinfunction "G_1") (pintype "passive"))
      (node (ref "R25") (pin "2") (pinfunction "2_2") (pintype "passive"))
    )
    (net (code "97") (name "/DRV33") (class "Default")
      (node (ref "Q21") (pin "1") (pinfunction "G_1") (pintype "passive"))
      (node (ref "R26") (pin "2") (pinfunction "2_2") (pintype "passive"))
    )
    (net (code "98") (name "/DRV34") (class "Default")
      (node (ref "Q22") (pin "1") (pinfunction "G_1") (pintype "passive"))
      (node (ref "R27") (pin "2") (pinfunction "2_2") (pintype "passive"))
    )
    (net (code "99") (name "/DRV35") (class "Default")
      (node (ref "Q23") (pin "1") (pinfunction "G_1") (pintype "passive"))
      (node (ref "R28") (pin "2") (pinfunction "2_2") (pintype "passive"))
    )
    (net (code "100") (name "/DRV36") (class "Default")
      (node (ref "Q24") (pin "1") (pinfunction "G_1") (pintype "passive"))
      (node (ref "R29") (pin "2") (pinfunction "2_2") (pintype "passive"))
    )
    (net (code "101") (name "/DRV37") (class "Default")
      (node (ref "Q25") (pin "1") (pinfunction "G_1") (pintype "passive"))
      (node (ref "R30") (pin "2") (pinfunction "2_2") (pintype "passive"))
    )
    (net (code "102") (name "/DRV38") (class "Default")
      (node (ref "Q26") (pin "1") (pinfunction "G_1") (pintype "passive"))
      (node (ref "R31") (pin "2") (pinfunction "2_2") (pintype "passive"))
    )
    (net (code "103") (name "/DRV39") (class "Default")
      (node (ref "Q11") (pin "1") (pinfunction "G_1") (pintype "passive"))
      (node (ref "R16") (pin "2") (pinfunction "2_2") (pintype "passive"))
    )
    (net (code "105") (name "5V0R") (class "Default")
      (node (ref "D14") (pin "2") (pinfunction "C_2") (pintype "passive"))
      (node (ref "D15") (pin "2") (pinfunction "C_2") (pintype "passive"))
      (node (ref "D16") (pin "2") (pinfunction "C_2") (pintype "passive"))
      (node (ref "D17") (pin "2") (pinfunction "C_2") (pintype "passive"))
      (node (ref "D18") (pin "2") (pinfunction "C_2") (pintype "passive"))
      (node (ref "D19") (pin "2") (pinfunction "C_2") (pintype "passive"))
      (node (ref "D20") (pin "2") (pinfunction "C_2") (pintype "passive"))
      (node (ref "D21") (pin "2") (pinfunction "C_2") (pintype "passive"))
      (node (ref "D22") (pin "2") (pinfunction "C_2") (pintype "passive"))
      (node (ref "D23") (pin "2") (pinfunction "C_2") (pintype "passive"))
      (node (ref "D24") (pin "2") (pinfunction "C_2") (pintype "passive"))
      (node (ref "D25") (pin "2") (pinfunction "C_2") (pintype "passive"))
      (node (ref "D26") (pin "2") (pinfunction "C_2") (pintype "passive"))
      (node (ref "D27") (pin "2") (pinfunction "C_2") (pintype "passive"))
      (node (ref "D28") (pin "2") (pinfunction "C_2") (pintype "passive"))
      (node (ref "D29") (pin "2") (pinfunction "C_2") (pintype "passive"))
      (node (ref "K12") (pin "1") (pinfunction "+_1") (pintype "passive"))
      (node (ref "K13") (pin "1") (pinfunction "+_1") (pintype "passive"))
      (node (ref "K14") (pin "1") (pinfunction "+_1") (pintype "passive"))
      (node (ref "K15") (pin "1") (pinfunction "+_1") (pintype "passive"))
      (node (ref "K16") (pin "1") (pinfunction "+_1") (pintype "passive"))
      (node (ref "K17") (pin "1") (pinfunction "+_1") (pintype "passive"))
      (node (ref "K18") (pin "1") (pinfunction "+_1") (pintype "passive"))
      (node (ref "K19") (pin "1") (pinfunction "+_1") (pintype "passive"))
      (node (ref "K20") (pin "1") (pinfunction "+_1") (pintype "passive"))
      (node (ref "K21") (pin "1") (pinfunction "+_1") (pintype "passive"))
      (node (ref "K22") (pin "1") (pinfunction "+_1") (pintype "passive"))
      (node (ref "K23") (pin "1") (pinfunction "+_1") (pintype "passive"))
      (node (ref "K24") (pin "1") (pinfunction "+_1") (pintype "passive"))
      (node (ref "K25") (pin "1") (pinfunction "+_1") (pintype "passive"))
      (node (ref "K26") (pin "1") (pinfunction "+_1") (pintype "passive"))
      (node (ref "K27") (pin "1") (pinfunction "+_1") (pintype "passive"))
    )
    (net (code "106") (name "GND") (class "Default")
      (node (ref "Q11") (pin "2") (pinfunction "S_2") (pintype "passive"))
      (node (ref "Q12") (pin "2") (pinfunction "S_2") (pintype "passive"))
      (node (ref "Q13") (pin "2") (pinfunction "S_2") (pintype "passive"))
      (node (ref "Q14") (pin "2") (pinfunction "S_2") (pintype "passive"))
      (node (ref "Q15") (pin "2") (pinfunction "S_2") (pintype "passive"))
      (node (ref "Q16") (pin "2") (pinfunction "S_2") (pintype "passive"))
      (node (ref "Q17") (pin "2") (pinfunction "S_2") (pintype "passive"))
      (node (ref "Q18") (pin "2") (pinfunction "S_2") (pintype "passive"))
      (node (ref "Q19") (pin "2") (pinfunction "S_2") (pintype "passive"))
      (node (ref "Q20") (pin "2") (pinfunction "S_2") (pintype "passive"))
      (node (ref "Q21") (pin "2") (pinfunction "S_2") (pintype "passive"))
      (node (ref "Q22") (pin "2") (pinfunction "S_2") (pintype "passive"))
      (node (ref "Q23") (pin "2") (pinfunction "S_2") (pintype "passive"))
      (node (ref "Q24") (pin "2") (pinfunction "S_2") (pintype "passive"))
      (node (ref "Q25") (pin "2") (pinfunction "S_2") (pintype "passive"))
      (node (ref "Q26") (pin "2") (pinfunction "S_2") (pintype "passive"))
      (node (ref "R16") (pin "1") (pinfunction "1_1") (pintype "passive"))
      (node (ref "R17") (pin "1") (pinfunction "1_1") (pintype "passive"))
      (node (ref "R18") (pin "1") (pinfunction "1_1") (pintype "passive"))
      (node (ref "R19") (pin "1") (pinfunction "1_1") (pintype "passive"))
      (node (ref "R20") (pin "1") (pinfunction "1_1") (pintype "passive"))
      (node (ref "R21") (pin "1") (pinfunction "1_1") (pintype "passive"))
      (node (ref "R22") (pin "1") (pinfunction "1_1") (pintype "passive"))
      (node (ref "R23") (pin "1") (pinfunction "1_1") (pintype "passive"))
      (node (ref "R24") (pin "1") (pinfunction "1_1") (pintype "passive"))
      (node (ref "R25") (pin "1") (pinfunction "1_1") (pintype "passive"))
      (node (ref "R26") (pin "1") (pinfunction "1_1") (pintype "passive"))
      (node (ref "R27") (pin "1") (pinfunction "1_1") (pintype "passive"))
      (node (ref "R28") (pin "1") (pinfunction "1_1") (pintype "passive"))
      (node (ref "R29") (pin "1") (pinfunction "1_1") (pintype "passive"))
      (node (ref "R30") (pin "1") (pinfunction "1_1") (pintype "passive"))
      (node (ref "R31") (pin "1") (pinfunction "1_1") (pintype "passive"))
    )
    (net (code "107") (name "Net-(D14-A)") (class "Default")
      (node (ref "D14") (pin "1") (pinfunction "A_1") (pintype "passive"))
      (node (ref "K12") (pin "5") (pinfunction "-_5") (pintype "passive"))
      (node (ref "Q12") (pin "3") (pinfunction "D_3") (pintype "passive"))
    )
    (net (code "108") (name "Net-(D15-A)") (class "Default")
      (node (ref "D15") (pin "1") (pinfunction "A_1") (pintype "passive"))
      (node (ref "K13") (pin "5") (pinfunction "-_5") (pintype "passive"))
      (node (ref "Q13") (pin "3") (pinfunction "D_3") (pintype "passive"))
    )
    (net (code "109") (name "Net-(D16-A)") (class "Default")
      (node (ref "D16") (pin "1") (pinfunction "A_1") (pintype "passive"))
      (node (ref "K14") (pin "5") (pinfunction "-_5") (pintype "passive"))
      (node (ref "Q14") (pin "3") (pinfunction "D_3") (pintype "passive"))
    )
    (net (code "110") (name "Net-(D17-A)") (class "Default")
      (node (ref "D17") (pin "1") (pinfunction "A_1") (pintype "passive"))
      (node (ref "K15") (pin "5") (pinfunction "-_5") (pintype "passive"))
      (node (ref "Q15") (pin "3") (pinfunction "D_3") (pintype "passive"))
    )
    (net (code "111") (name "Net-(D18-A)") (class "Default")
      (node (ref "D18") (pin "1") (pinfunction "A_1") (pintype "passive"))
      (node (ref "K16") (pin "5") (pinfunction "-_5") (pintype "passive"))
      (node (ref "Q16") (pin "3") (pinfunction "D_3") (pintype "passive"))
    )
    (net (code "112") (name "Net-(D19-A)") (class "Default")
      (node (ref "D19") (pin "1") (pinfunction "A_1") (pintype "passive"))
      (node (ref "K17") (pin "5") (pinfunction "-_5") (pintype "passive"))
      (node (ref "Q17") (pin "3") (pinfunction "D_3") (pintype "passive"))
    )
    (net (code "113") (name "Net-(D20-A)") (class "Default")
      (node (ref "D20") (pin "1") (pinfunction "A_1") (pintype "passive"))
      (node (ref "K18") (pin "5") (pinfunction "-_5") (pintype "passive"))
      (node (ref "Q18") (pin "3") (pinfunction "D_3") (pintype "passive"))
    )
    (net (code "114") (name "Net-(D21-A)") (class "Default")
      (node (ref "D21") (pin "1") (pinfunction "A_1") (pintype "passive"))
      (node (ref "K19") (pin "5") (pinfunction "-_5") (pintype "passive"))
      (node (ref "Q19") (pin "3") (pinfunction "D_3") (pintype "passive"))
    )
    (net (code "115") (name "Net-(D22-A)") (class "Default")
      (node (ref "D22") (pin "1") (pinfunction "A_1") (pintype "passive"))
      (node (ref "K20") (pin "5") (pinfunction "-_5") (pintype "passive"))
      (node (ref "Q20") (pin "3") (pinfunction "D_3") (pintype "passive"))
    )
    (net (code "116") (name "Net-(D23-A)") (class "Default")
      (node (ref "D23") (pin "1") (pinfunction "A_1") (pintype "passive"))
      (node (ref "K21") (pin "5") (pinfunction "-_5") (pintype "passive"))
      (node (ref "Q21") (pin "3") (pinfunction "D_3") (pintype "passive"))
    )
    (net (code "117") (name "Net-(D24-A)") (class "Default")
      (node (ref "D24") (pin "1") (pinfunction "A_1") (pintype "passive"))
      (node (ref "K22") (pin "5") (pinfunction "-_5") (pintype "passive"))
      (node (ref "Q22") (pin "3") (pinfunction "D_3") (pintype "passive"))
    )
    (net (code "118") (name "Net-(D25-A)") (class "Default")
      (node (ref "D25") (pin "1") (pinfunction "A_1") (pintype "passive"))
      (node (ref "K23") (pin "5") (pinfunction "-_5") (pintype "passive"))
      (node (ref "Q23") (pin "3") (pinfunction "D_3") (pintype "passive"))
    )
    (net (code "119") (name "Net-(D26-A)") (class "Default")
      (node (ref "D26") (pin "1") (pinfunction "A_1") (pintype "passive"))
      (node (ref "K24") (pin "5") (pinfunction "-_5") (pintype "passive"))
      (node (ref "Q24") (pin "3") (pinfunction "D_3") (pintype "passive"))
    )
    (net (code "120") (name "Net-(D27-A)") (class "Default")
      (node (ref "D27") (pin "1") (pinfunction "A_1") (pintype "passive"))
      (node (ref "K25") (pin "5") (pinfunction "-_5") (pintype "passive"))
      (node (ref "Q25") (pin "3") (pinfunction "D_3") (pintype "passive"))
    )
    (net (code "121") (name "Net-(D28-A)") (class "Default")
      (node (ref "D28") (pin "1") (pinfunction "A_1") (pintype "passive"))
      (node (ref "K26") (pin "5") (pinfunction "-_5") (pintype "passive"))
      (node (ref "Q26") (pin "3") (pinfunction "D_3") (pintype "passive"))
    )
    (net (code "122") (name "Net-(D29-A)") (class "Default")
      (node (ref "D29") (pin "1") (pinfunction "A_1") (pintype "passive"))
      (node (ref "K27") (pin "5") (pinfunction "-_5") (pintype "passive"))
      (node (ref "Q11") (pin "3") (pinfunction "D_3") (pintype "passive"))
    )
    (net (code "123") (name "Net-(K12A-Cin)") (class "Default")
      (node (ref "K12") (pin "2") (pinfunction "Cin_2") (pintype "passive"))
      (node (ref "X6") (pin "1") (pinfunction "+_1") (pintype "passive"))
    )
    (net (code "124") (name "Net-(K12A-Cno)") (class "Default")
      (node (ref "K12") (pin "3") (pinfunction "Cno_3") (pintype "passive"))
      (node (ref "X5") (pin "2") (pinfunction "2_2") (pintype "passive"))
    )
    (net (code "125") (name "Net-(K13A-Cin)") (class "Default")
      (node (ref "K13") (pin "2") (pinfunction "Cin_2") (pintype "passive"))
      (node (ref "X6") (pin "2") (pinfunction "-_2") (pintype "passive"))
    )
    (net (code "126") (name "Net-(K13A-Cno)") (class "Default")
      (node (ref "K13") (pin "3") (pinfunction "Cno_3") (pintype "passive"))
      (node (ref "X5") (pin "1") (pinfunction "1_1") (pintype "passive"))
    )
    (net (code "127") (name "Net-(K14A-Cin)") (class "Default")
      (node (ref "K14") (pin "2") (pinfunction "Cin_2") (pintype "passive"))
      (node (ref "X9") (pin "1") (pinfunction "+_1") (pintype "passive"))
    )
    (net (code "128") (name "Net-(K14A-Cno)") (class "Default")
      (node (ref "K14") (pin "3") (pinfunction "Cno_3") (pintype "passive"))
      (node (ref "X8") (pin "2") (pinfunction "2_2") (pintype "passive"))
    )
    (net (code "129") (name "Net-(K15A-Cin)") (class "Default")
      (node (ref "K15") (pin "2") (pinfunction "Cin_2") (pintype "passive"))
      (node (ref "X9") (pin "2") (pinfunction "-_2") (pintype "passive"))
    )
    (net (code "130") (name "Net-(K15A-Cno)") (class "Default")
      (node (ref "K15") (pin "3") (pinfunction "Cno_3") (pintype "passive"))
      (node (ref "X8") (pin "1") (pinfunction "1_1") (pintype "passive"))
    )
    (net (code "131") (name "Net-(K16A-Cin)") (class "Default")
      (node (ref "K16") (pin "2") (pinfunction "Cin_2") (pintype "passive"))
      (node (ref "X12") (pin "1") (pinfunction "+_1") (pintype "passive"))
    )
    (net (code "132") (name "Net-(K16A-Cno)") (class "Default")
      (node (ref "K16") (pin "3") (pinfunction "Cno_3") (pintype "passive"))
      (node (ref "X11") (pin "2") (pinfunction "2_2") (pintype "passive"))
    )
    (net (code "133") (name "Net-(K17A-Cin)") (class "Default")
      (node (ref "K17") (pin "2") (pinfunction "Cin_2") (pintype "passive"))
      (node (ref "X12") (pin "2") (pinfunction "-_2") (pintype "passive"))
    )
    (net (code "134") (name "Net-(K17A-Cno)") (class "Default")
      (node (ref "K17") (pin "3") (pinfunction "Cno_3") (pintype "passive"))
      (node (ref "X11") (pin "1") (pinfunction "1_1") (pintype "passive"))
    )
    (net (code "135") (name "Net-(K18A-Cin)") (class "Default")
      (node (ref "K18") (pin "2") (pinfunction "Cin_2") (pintype "passive"))
      (node (ref "X13") (pin "1") (pinfunction "+_1") (pintype "passive"))
    )
    (net (code "136") (name "Net-(K18A-Cno)") (class "Default")
      (node (ref "K18") (pin "3") (pinfunction "Cno_3") (pintype "passive"))
      (node (ref "X14") (pin "2") (pinfunction "2_2") (pintype "passive"))
    )
    (net (code "137") (name "Net-(K19A-Cin)") (class "Default")
      (node (ref "K19") (pin "2") (pinfunction "Cin_2") (pintype "passive"))
      (node (ref "X13") (pin "2") (pinfunction "-_2") (pintype "passive"))
    )
    (net (code "138") (name "Net-(K19A-Cno)") (class "Default")
      (node (ref "K19") (pin "3") (pinfunction "Cno_3") (pintype "passive"))
      (node (ref "X14") (pin "1") (pinfunction "1_1") (pintype "passive"))
    )
    (net (code "139") (name "Net-(K20A-Cin)") (class "Default")
      (node (ref "K20") (pin "2") (pinfunction "Cin_2") (pintype "passive"))
      (node (ref "X16") (pin "1") (pinfunction "+_1") (pintype "passive"))
    )
    (net (code "140") (name "Net-(K20A-Cno)") (class "Default")
      (node (ref "K20") (pin "3") (pinfunction "Cno_3") (pintype "passive"))
      (node (ref "X18") (pin "2") (pinfunction "2_2") (pintype "passive"))
    )
    (net (code "141") (name "Net-(K21A-Cin)") (class "Default")
      (node (ref "K21") (pin "2") (pinfunction "Cin_2") (pintype "passive"))
      (node (ref "X16") (pin "2") (pinfunction "-_2") (pintype "passive"))
    )
    (net (code "142") (name "Net-(K21A-Cno)") (class "Default")
      (node (ref "K21") (pin "3") (pinfunction "Cno_3") (pintype "passive"))
      (node (ref "X18") (pin "1") (pinfunction "1_1") (pintype "passive"))
    )
    (net (code "143") (name "Net-(K22A-Cin)") (class "Default")
      (node (ref "K22") (pin "2") (pinfunction "Cin_2") (pintype "passive"))
      (node (ref "X19") (pin "1") (pinfunction "+_1") (pintype "passive"))
    )
    (net (code "144") (name "Net-(K22A-Cno)") (class "Default")
      (node (ref "K22") (pin "3") (pinfunction "Cno_3") (pintype "passive"))
      (node (ref "X20") (pin "2") (pinfunction "2_2") (pintype "passive"))
    )
    (net (code "145") (name "Net-(K23A-Cin)") (class "Default")
      (node (ref "K23") (pin "2") (pinfunction "Cin_2") (pintype "passive"))
      (node (ref "X19") (pin "2") (pinfunction "-_2") (pintype "passive"))
    )
    (net (code "146") (name "Net-(K23A-Cno)") (class "Default")
      (node (ref "K23") (pin "3") (pinfunction "Cno_3") (pintype "passive"))
      (node (ref "X20") (pin "1") (pinfunction "1_1") (pintype "passive"))
    )
    (net (code "147") (name "Net-(K24A-Cin)") (class "Default")
      (node (ref "K24") (pin "2") (pinfunction "Cin_2") (pintype "passive"))
      (node (ref "X22") (pin "1") (pinfunction "+_1") (pintype "passive"))
    )
    (net (code "148") (name "Net-(K24A-Cno)") (class "Default")
      (node (ref "K24") (pin "3") (pinfunction "Cno_3") (pintype "passive"))
      (node (ref "X23") (pin "2") (pinfunction "2_2") (pintype "passive"))
    )
    (net (code "149") (name "Net-(K25A-Cin)") (class "Default")
      (node (ref "K25") (pin "2") (pinfunction "Cin_2") (pintype "passive"))
      (node (ref "X22") (pin "2") (pinfunction "-_2") (pintype "passive"))
    )
    (net (code "150") (name "Net-(K25A-Cno)") (class "Default")
      (node (ref "K25") (pin "3") (pinfunction "Cno_3") (pintype "passive"))
      (node (ref "X23") (pin "1") (pinfunction "1_1") (pintype "passive"))
    )
    (net (code "151") (name "Net-(K26A-Cin)") (class "Default")
      (node (ref "K26") (pin "2") (pinfunction "Cin_2") (pintype "passive"))
      (node (ref "X24") (pin "1") (pinfunction "+_1") (pintype "passive"))
    )
    (net (code "152") (name "Net-(K26A-Cno)") (class "Default")
      (node (ref "K26") (pin "3") (pinfunction "Cno_3") (pintype "passive"))
      (node (ref "X26") (pin "2") (pinfunction "2_2") (pintype "passive"))
    )
    (net (code "153") (name "Net-(K27A-Cin)") (class "Default")
      (node (ref "K27") (pin "2") (pinfunction "Cin_2") (pintype "passive"))
      (node (ref "X24") (pin "2") (pinfunction "-_2") (pintype "passive"))
    )
    (net (code "154") (name "Net-(K27A-Cno)") (class "Default")
      (node (ref "K27") (pin "3") (pinfunction "Cno_3") (pintype "passive"))
      (node (ref "X26") (pin "1") (pinfunction "1_1") (pintype "passive"))
    )
    (net (code "155") (name "unconnected-(K12A-Cnc-Pad4)") (class "Default")
      (node (ref "K12") (pin "4") (pinfunction "Cnc_4") (pintype "passive+no_connect"))
    )
    (net (code "156") (name "unconnected-(K13A-Cnc-Pad4)") (class "Default")
      (node (ref "K13") (pin "4") (pinfunction "Cnc_4") (pintype "passive+no_connect"))
    )
    (net (code "157") (name "unconnected-(K14A-Cnc-Pad4)") (class "Default")
      (node (ref "K14") (pin "4") (pinfunction "Cnc_4") (pintype "passive+no_connect"))
    )
    (net (code "158") (name "unconnected-(K15A-Cnc-Pad4)") (class "Default")
      (node (ref "K15") (pin "4") (pinfunction "Cnc_4") (pintype "passive+no_connect"))
    )
    (net (code "159") (name "unconnected-(K16A-Cnc-Pad4)") (class "Default")
      (node (ref "K16") (pin "4") (pinfunction "Cnc_4") (pintype "passive+no_connect"))
    )
    (net (code "160") (name "unconnected-(K17A-Cnc-Pad4)") (class "Default")
      (node (ref "K17") (pin "4") (pinfunction "Cnc_4") (pintype "passive+no_connect"))
    )
    (net (code "161") (name "unconnected-(K18A-Cnc-Pad4)") (class "Default")
      (node (ref "K18") (pin "4") (pinfunction "Cnc_4") (pintype "passive+no_connect"))
    )
    (net (code "162") (name "unconnected-(K19A-Cnc-Pad4)") (class "Default")
      (node (ref "K19") (pin "4") (pinfunction "Cnc_4") (pintype "passive+no_connect"))
    )
    (net (code "163") (name "unconnected-(K20A-Cnc-Pad4)") (class "Default")
      (node (ref "K20") (pin "4") (pinfunction "Cnc_4") (pintype "passive+no_connect"))
    )
    (net (code "164") (name "unconnected-(K21A-Cnc-Pad4)") (class "Default")
      (node (ref "K21") (pin "4") (pinfunction "Cnc_4") (pintype "passive+no_connect"))
    )
    (net (code "165") (name "unconnected-(K22A-Cnc-Pad4)") (class "Default")
      (node (ref "K22") (pin "4") (pinfunction "Cnc_4") (pintype "passive+no_connect"))
    )
    (net (code "166") (name "unconnected-(K23A-Cnc-Pad4)") (class "Default")
      (node (ref "K23") (pin "4") (pinfunction "Cnc_4") (pintype "passive+no_connect"))
    )
    (net (code "167") (name "unconnected-(K24A-Cnc-Pad4)") (class "Default")
      (node (ref "K24") (pin "4") (pinfunction "Cnc_4") (pintype "passive+no_connect"))
    )
    (net (code "168") (name "unconnected-(K25A-Cnc-Pad4)") (class "Default")
      (node (ref "K25") (pin "4") (pinfunction "Cnc_4") (pintype "passive+no_connect"))
    )
    (net (code "169") (name "unconnected-(K26A-Cnc-Pad4)") (class "Default")
      (node (ref "K26") (pin "4") (pinfunction "Cnc_4") (pintype "passive+no_connect"))
    )
    (net (code "170") (name "unconnected-(K27A-Cnc-Pad4)") (class "Default")
      (node (ref "K27") (pin "4") (pinfunction "Cnc_4") (pintype "passive+no_connect"))
    )
  )
)
